# HAB_Schematic.net
KiCad netlist of a schematic drawn in Altium Designer
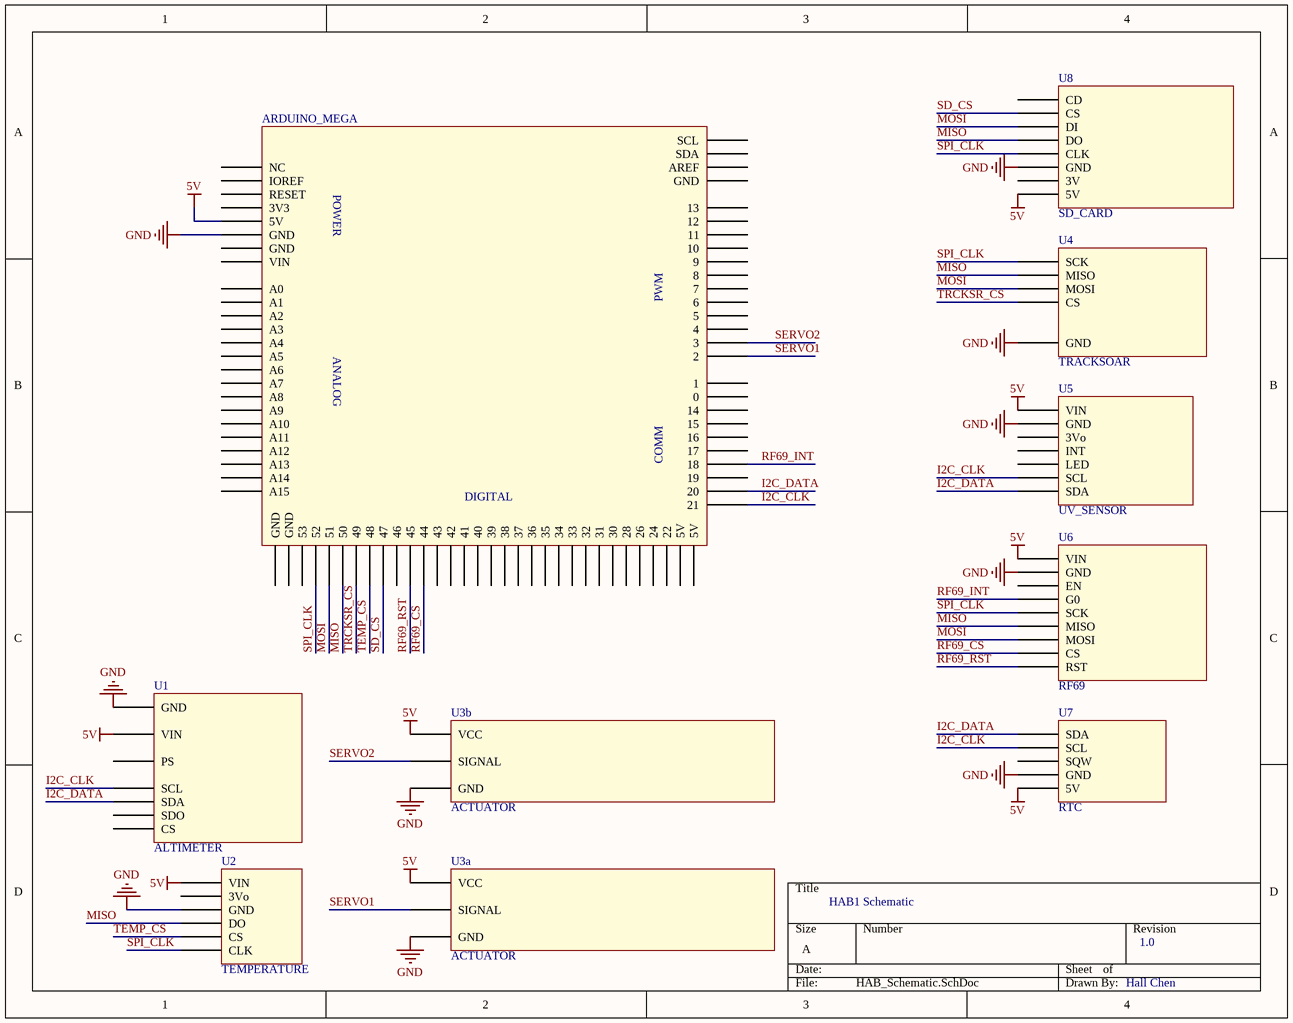
[diagram p0: HAB_Schematic.SchDoc]

(export (version "E")
  (design (tool "Eeschema 10.0.6"))
  (components
    (comp (ref "ARDUINO_MEGA")
      (value "ARDUINO_MEGA")
      (libsource (lib "HAB_Schematic_lib") (part "ARDUINO_MEGA"))
    )
    (comp (ref "U1") (value "ALTIMETER") (libsource (lib "HAB_Schematic_lib") (part "ALTIMETER")))
    (comp (ref "U2") (value "TEMPERATURE") (libsource (lib "HAB_Schematic_lib") (part "TEMPERATURE")))
    (comp (ref "U3a") (value "ACTUATOR") (libsource (lib "HAB_Schematic_lib") (part "ACTUATOR")))
    (comp (ref "U3b") (value "ACTUATOR") (libsource (lib "HAB_Schematic_lib") (part "ACTUATOR")))
    (comp (ref "U4") (value "TRACKSOAR") (libsource (lib "HAB_Schematic_lib") (part "TRACKSOAR")))
    (comp (ref "U5") (value "UV_SENSOR") (libsource (lib "HAB_Schematic_lib") (part "UV_SENSOR")))
    (comp (ref "U6") (value "RF69") (libsource (lib "HAB_Schematic_lib") (part "RF69")))
    (comp (ref "U7") (value "RTC") (libsource (lib "HAB_Schematic_lib") (part "RTC")))
    (comp (ref "U8") (value "SD_CARD") (libsource (lib "HAB_Schematic_lib") (part "SD_CARD")))
  )
  (nets
    (net (code "1") (name "/I2C_CLK") (class "Default")
      (node (ref "ARDUINO_MEGA") (pin "73") (pinfunction "21_73") (pintype "passive"))
      (node (ref "U1") (pin "4") (pinfunction "SCL_4") (pintype "passive"))
      (node (ref "U5") (pin "6") (pinfunction "SCL_6") (pintype "passive"))
      (node (ref "U7") (pin "2") (pinfunction "SCL_2") (pintype "passive"))
    )
    (net (code "2") (name "/I2C_DATA") (class "Default")
      (node (ref "ARDUINO_MEGA") (pin "72") (pinfunction "20_72") (pintype "passive"))
      (node (ref "U1") (pin "5") (pinfunction "SDA_5") (pintype "passive"))
      (node (ref "U5") (pin "7") (pinfunction "SDA_7") (pintype "passive"))
      (node (ref "U7") (pin "1") (pinfunction "SDA_1") (pintype "passive"))
    )
    (net (code "3") (name "/MISO") (class "Default")
      (node (ref "ARDUINO_MEGA") (pin "39") (pinfunction "50_39") (pintype "passive"))
      (node (ref "U2") (pin "4") (pinfunction "DO_4") (pintype "passive"))
      (node (ref "U4") (pin "1") (pinfunction "MISO_1") (pintype "passive"))
      (node (ref "U6") (pin "6") (pinfunction "MISO_6") (pintype "passive"))
      (node (ref "U8") (pin "4") (pinfunction "DO_4") (pintype "passive"))
    )
    (net (code "4") (name "/MOSI") (class "Default")
      (node (ref "ARDUINO_MEGA") (pin "40") (pinfunction "51_40") (pintype "passive"))
      (node (ref "U4") (pin "2") (pinfunction "MOSI_2") (pintype "passive"))
      (node (ref "U6") (pin "7") (pinfunction "MOSI_7") (pintype "passive"))
      (node (ref "U8") (pin "3") (pinfunction "DI_3") (pintype "passive"))
    )
    (net (code "5") (name "/RF69_CS") (class "Default")
      (node (ref "ARDUINO_MEGA") (pin "33") (pinfunction "44_33") (pintype "passive"))
      (node (ref "U6") (pin "8") (pinfunction "CS_8") (pintype "passive"))
    )
    (net (code "6") (name "/RF69_INT") (class "Default")
      (node (ref "ARDUINO_MEGA") (pin "70") (pinfunction "18_70") (pintype "passive"))
      (node (ref "U6") (pin "4") (pinfunction "G0_4") (pintype "passive"))
    )
    (net (code "7") (name "/RF69_RST") (class "Default")
      (node (ref "ARDUINO_MEGA") (pin "34") (pinfunction "45_34") (pintype "passive"))
      (node (ref "U6") (pin "9") (pinfunction "RST_9") (pintype "passive"))
    )
    (net (code "8") (name "/SD_CS") (class "Default")
      (node (ref "ARDUINO_MEGA") (pin "36") (pinfunction "47_36") (pintype "passive"))
      (node (ref "U8") (pin "2") (pinfunction "CS_2") (pintype "passive"))
    )
    (net (code "9") (name "/SERVO1") (class "Default")
      (node (ref "ARDUINO_MEGA") (pin "50") (pinfunction "2_50") (pintype "passive"))
      (node (ref "U3a") (pin "1") (pinfunction "SIGNAL_1") (pintype "passive"))
    )
    (net (code "10") (name "/SERVO2") (class "Default")
      (node (ref "ARDUINO_MEGA") (pin "51") (pinfunction "3_51") (pintype "passive"))
      (node (ref "U3b") (pin "1") (pinfunction "SIGNAL_1") (pintype "passive"))
    )
    (net (code "11") (name "/SPI_CLK") (class "Default")
      (node (ref "ARDUINO_MEGA") (pin "41") (pinfunction "52_41") (pintype "passive"))
      (node (ref "U2") (pin "6") (pinfunction "CLK_6") (pintype "passive"))
      (node (ref "U4") (pin "4") (pinfunction "SCK_4") (pintype "passive"))
      (node (ref "U6") (pin "5") (pinfunction "SCK_5") (pintype "passive"))
      (node (ref "U8") (pin "5") (pinfunction "CLK_5") (pintype "passive"))
    )
    (net (code "12") (name "/TEMP_CS") (class "Default")
      (node (ref "ARDUINO_MEGA") (pin "37") (pinfunction "48_37") (pintype "passive"))
      (node (ref "U2") (pin "5") (pinfunction "CS_5") (pintype "passive"))
    )
    (net (code "13") (name "/TRCKSR_CS") (class "Default")
      (node (ref "ARDUINO_MEGA") (pin "38") (pinfunction "49_38") (pintype "passive"))
      (node (ref "U4") (pin "3") (pinfunction "CS_3") (pintype "passive"))
    )
    (net (code "14") (name "5V") (class "Default")
      (node (ref "ARDUINO_MEGA") (pin "5") (pinfunction "5V_5") (pintype "passive"))
      (node (ref "U1") (pin "2") (pinfunction "VIN_2") (pintype "passive"))
      (node (ref "U2") (pin "1") (pinfunction "VIN_1") (pintype "passive"))
      (node (ref "U3a") (pin "0") (pinfunction "VCC_0") (pintype "passive"))
      (node (ref "U3b") (pin "0") (pinfunction "VCC_0") (pintype "passive"))
      (node (ref "U5") (pin "1") (pinfunction "VIN_1") (pintype "passive"))
      (node (ref "U6") (pin "1") (pinfunction "VIN_1") (pintype "passive"))
      (node (ref "U7") (pin "5") (pinfunction "5V_5") (pintype "passive"))
      (node (ref "U8") (pin "8") (pinfunction "5V_8") (pintype "passive"))
    )
    (net (code "15") (name "GND") (class "Default")
      (node (ref "ARDUINO_MEGA") (pin "6") (pinfunction "GND_6") (pintype "passive"))
      (node (ref "U1") (pin "1") (pinfunction "GND_1") (pintype "passive"))
      (node (ref "U2") (pin "3") (pinfunction "GND_3") (pintype "passive"))
      (node (ref "U3a") (pin "2") (pinfunction "GND_2") (pintype "passive"))
      (node (ref "U3b") (pin "2") (pinfunction "GND_2") (pintype "passive"))
      (node (ref "U4") (pin "5") (pinfunction "GND_5") (pintype "passive"))
      (node (ref "U5") (pin "2") (pinfunction "GND_2") (pintype "passive"))
      (node (ref "U6") (pin "2") (pinfunction "GND_2") (pintype "passive"))
      (node (ref "U7") (pin "4") (pinfunction "GND_4") (pintype "passive"))
      (node (ref "U8") (pin "6") (pinfunction "GND_6") (pintype "passive"))
    )
    (net (code "16") (name "unconnected-(ARDUINO_MEGA-0-Pad48)") (class "Default")
      (node (ref "ARDUINO_MEGA") (pin "48") (pinfunction "0_48") (pintype "passive"))
    )
    (net (code "17") (name "unconnected-(ARDUINO_MEGA-1-Pad49)") (class "Default")
      (node (ref "ARDUINO_MEGA") (pin "49") (pinfunction "1_49") (pintype "passive"))
    )
    (net (code "18") (name "unconnected-(ARDUINO_MEGA-3V3-Pad4)") (class "Default")
      (node (ref "ARDUINO_MEGA") (pin "4") (pinfunction "3V3_4") (pintype "passive"))
    )
    (net (code "19") (name "unconnected-(ARDUINO_MEGA-4-Pad52)") (class "Default")
      (node (ref "ARDUINO_MEGA") (pin "52") (pinfunction "4_52") (pintype "passive"))
    )
    (net (code "20") (name "unconnected-(ARDUINO_MEGA-5-Pad53)") (class "Default")
      (node (ref "ARDUINO_MEGA") (pin "53") (pinfunction "5_53") (pintype "passive"))
    )
    (net (code "21") (name "unconnected-(ARDUINO_MEGA-5V-Pad46)") (class "Default")
      (node (ref "ARDUINO_MEGA") (pin "46") (pinfunction "5V_46") (pintype "passive"))
    )
    (net (code "22") (name "unconnected-(ARDUINO_MEGA-5V-Pad47)") (class "Default")
      (node (ref "ARDUINO_MEGA") (pin "47") (pinfunction "5V_47") (pintype "passive"))
    )
    (net (code "23") (name "unconnected-(ARDUINO_MEGA-6-Pad54)") (class "Default")
      (node (ref "ARDUINO_MEGA") (pin "54") (pinfunction "6_54") (pintype "passive"))
    )
    (net (code "24") (name "unconnected-(ARDUINO_MEGA-7-Pad55)") (class "Default")
      (node (ref "ARDUINO_MEGA") (pin "55") (pinfunction "7_55") (pintype "passive"))
    )
    (net (code "25") (name "unconnected-(ARDUINO_MEGA-8-Pad56)") (class "Default")
      (node (ref "ARDUINO_MEGA") (pin "56") (pinfunction "8_56") (pintype "passive"))
    )
    (net (code "26") (name "unconnected-(ARDUINO_MEGA-9-Pad57)") (class "Default")
      (node (ref "ARDUINO_MEGA") (pin "57") (pinfunction "9_57") (pintype "passive"))
    )
    (net (code "27") (name "unconnected-(ARDUINO_MEGA-10-Pad58)") (class "Default")
      (node (ref "ARDUINO_MEGA") (pin "58") (pinfunction "10_58") (pintype "passive"))
    )
    (net (code "28") (name "unconnected-(ARDUINO_MEGA-11-Pad59)") (class "Default")
      (node (ref "ARDUINO_MEGA") (pin "59") (pinfunction "11_59") (pintype "passive"))
    )
    (net (code "29") (name "unconnected-(ARDUINO_MEGA-12-Pad60)") (class "Default")
      (node (ref "ARDUINO_MEGA") (pin "60") (pinfunction "12_60") (pintype "passive"))
    )
    (net (code "30") (name "unconnected-(ARDUINO_MEGA-13-Pad61)") (class "Default")
      (node (ref "ARDUINO_MEGA") (pin "61") (pinfunction "13_61") (pintype "passive"))
    )
    (net (code "31") (name "unconnected-(ARDUINO_MEGA-14-Pad66)") (class "Default")
      (node (ref "ARDUINO_MEGA") (pin "66") (pinfunction "14_66") (pintype "passive"))
    )
    (net (code "32") (name "unconnected-(ARDUINO_MEGA-15-Pad67)") (class "Default")
      (node (ref "ARDUINO_MEGA") (pin "67") (pinfunction "15_67") (pintype "passive"))
    )
    (net (code "33") (name "unconnected-(ARDUINO_MEGA-16-Pad68)") (class "Default")
      (node (ref "ARDUINO_MEGA") (pin "68") (pinfunction "16_68") (pintype "passive"))
    )
    (net (code "34") (name "unconnected-(ARDUINO_MEGA-17-Pad69)") (class "Default")
      (node (ref "ARDUINO_MEGA") (pin "69") (pinfunction "17_69") (pintype "passive"))
    )
    (net (code "35") (name "unconnected-(ARDUINO_MEGA-19-Pad71)") (class "Default")
      (node (ref "ARDUINO_MEGA") (pin "71") (pinfunction "19_71") (pintype "passive"))
    )
    (net (code "36") (name "unconnected-(ARDUINO_MEGA-22-Pad45)") (class "Default")
      (node (ref "ARDUINO_MEGA") (pin "45") (pinfunction "22_45") (pintype "passive"))
    )
    (net (code "37") (name "unconnected-(ARDUINO_MEGA-24-Pad44)") (class "Default")
      (node (ref "ARDUINO_MEGA") (pin "44") (pinfunction "24_44") (pintype "passive"))
    )
    (net (code "38") (name "unconnected-(ARDUINO_MEGA-26-Pad43)") (class "Default")
      (node (ref "ARDUINO_MEGA") (pin "43") (pinfunction "26_43") (pintype "passive"))
    )
    (net (code "39") (name "unconnected-(ARDUINO_MEGA-28-Pad42)") (class "Default")
      (node (ref "ARDUINO_MEGA") (pin "42") (pinfunction "28_42") (pintype "passive"))
    )
    (net (code "40") (name "unconnected-(ARDUINO_MEGA-30-Pad19)") (class "Default")
      (node (ref "ARDUINO_MEGA") (pin "19") (pinfunction "30_19") (pintype "passive"))
    )
    (net (code "41") (name "unconnected-(ARDUINO_MEGA-31-Pad20)") (class "Default")
      (node (ref "ARDUINO_MEGA") (pin "20") (pinfunction "31_20") (pintype "passive"))
    )
    (net (code "42") (name "unconnected-(ARDUINO_MEGA-32-Pad21)") (class "Default")
      (node (ref "ARDUINO_MEGA") (pin "21") (pinfunction "32_21") (pintype "passive"))
    )
    (net (code "43") (name "unconnected-(ARDUINO_MEGA-33-Pad22)") (class "Default")
      (node (ref "ARDUINO_MEGA") (pin "22") (pinfunction "33_22") (pintype "passive"))
    )
    (net (code "44") (name "unconnected-(ARDUINO_MEGA-34-Pad23)") (class "Default")
      (node (ref "ARDUINO_MEGA") (pin "23") (pinfunction "34_23") (pintype "passive"))
    )
    (net (code "45") (name "unconnected-(ARDUINO_MEGA-35-Pad24)") (class "Default")
      (node (ref "ARDUINO_MEGA") (pin "24") (pinfunction "35_24") (pintype "passive"))
    )
    (net (code "46") (name "unconnected-(ARDUINO_MEGA-36-Pad25)") (class "Default")
      (node (ref "ARDUINO_MEGA") (pin "25") (pinfunction "36_25") (pintype "passive"))
    )
    (net (code "47") (name "unconnected-(ARDUINO_MEGA-37-Pad26)") (class "Default")
      (node (ref "ARDUINO_MEGA") (pin "26") (pinfunction "37_26") (pintype "passive"))
    )
    (net (code "48") (name "unconnected-(ARDUINO_MEGA-38-Pad27)") (class "Default")
      (node (ref "ARDUINO_MEGA") (pin "27") (pinfunction "38_27") (pintype "passive"))
    )
    (net (code "49") (name "unconnected-(ARDUINO_MEGA-39-Pad28)") (class "Default")
      (node (ref "ARDUINO_MEGA") (pin "28") (pinfunction "39_28") (pintype "passive"))
    )
    (net (code "50") (name "unconnected-(ARDUINO_MEGA-40-Pad29)") (class "Default")
      (node (ref "ARDUINO_MEGA") (pin "29") (pinfunction "40_29") (pintype "passive"))
    )
    (net (code "51") (name "unconnected-(ARDUINO_MEGA-41-Pad30)") (class "Default")
      (node (ref "ARDUINO_MEGA") (pin "30") (pinfunction "41_30") (pintype "passive"))
    )
    (net (code "52") (name "unconnected-(ARDUINO_MEGA-42-Pad31)") (class "Default")
      (node (ref "ARDUINO_MEGA") (pin "31") (pinfunction "42_31") (pintype "passive"))
    )
    (net (code "53") (name "unconnected-(ARDUINO_MEGA-43-Pad32)") (class "Default")
      (node (ref "ARDUINO_MEGA") (pin "32") (pinfunction "43_32") (pintype "passive"))
    )
    (net (code "54") (name "unconnected-(ARDUINO_MEGA-46-Pad35)") (class "Default")
      (node (ref "ARDUINO_MEGA") (pin "35") (pinfunction "46_35") (pintype "passive"))
    )
    (net (code "55") (name "unconnected-(ARDUINO_MEGA-53-Pad18)") (class "Default")
      (node (ref "ARDUINO_MEGA") (pin "18") (pinfunction "53_18") (pintype "passive"))
    )
    (net (code "56") (name "unconnected-(ARDUINO_MEGA-A0-Pad9)") (class "Default")
      (node (ref "ARDUINO_MEGA") (pin "9") (pinfunction "A0_9") (pintype "passive"))
    )
    (net (code "57") (name "unconnected-(ARDUINO_MEGA-A1-Pad10)") (class "Default")
      (node (ref "ARDUINO_MEGA") (pin "10") (pinfunction "A1_10") (pintype "passive"))
    )
    (net (code "58") (name "unconnected-(ARDUINO_MEGA-A2-Pad2)") (class "Default")
      (node (ref "ARDUINO_MEGA") (pin "2") (pinfunction "A2_2") (pintype "passive"))
    )
    (net (code "59") (name "unconnected-(ARDUINO_MEGA-A3-Pad3)") (class "Default")
      (node (ref "ARDUINO_MEGA") (pin "3") (pinfunction "A3_3") (pintype "passive"))
    )
    (net (code "60") (name "unconnected-(ARDUINO_MEGA-A4-Pad4)") (class "Default")
      (node (ref "ARDUINO_MEGA") (pin "4") (pinfunction "A4_4") (pintype "passive"))
    )
    (net (code "61") (name "unconnected-(ARDUINO_MEGA-A5-Pad5)") (class "Default")
      (node (ref "ARDUINO_MEGA") (pin "5") (pinfunction "A5_5") (pintype "passive"))
    )
    (net (code "62") (name "unconnected-(ARDUINO_MEGA-A6-Pad6)") (class "Default")
      (node (ref "ARDUINO_MEGA") (pin "6") (pinfunction "A6_6") (pintype "passive"))
    )
    (net (code "63") (name "unconnected-(ARDUINO_MEGA-A7-Pad7)") (class "Default")
      (node (ref "ARDUINO_MEGA") (pin "7") (pinfunction "A7_7") (pintype "passive"))
    )
    (net (code "64") (name "unconnected-(ARDUINO_MEGA-A8-Pad8)") (class "Default")
      (node (ref "ARDUINO_MEGA") (pin "8") (pinfunction "A8_8") (pintype "passive"))
    )
    (net (code "65") (name "unconnected-(ARDUINO_MEGA-A9-Pad9)") (class "Default")
      (node (ref "ARDUINO_MEGA") (pin "9") (pinfunction "A9_9") (pintype "passive"))
    )
    (net (code "66") (name "unconnected-(ARDUINO_MEGA-A10-Pad10)") (class "Default")
      (node (ref "ARDUINO_MEGA") (pin "10") (pinfunction "A10_10") (pintype "passive"))
    )
    (net (code "67") (name "unconnected-(ARDUINO_MEGA-A11-Pad11)") (class "Default")
      (node (ref "ARDUINO_MEGA") (pin "11") (pinfunction "A11_11") (pintype "passive"))
    )
    (net (code "68") (name "unconnected-(ARDUINO_MEGA-A12-Pad12)") (class "Default")
      (node (ref "ARDUINO_MEGA") (pin "12") (pinfunction "A12_12") (pintype "passive"))
    )
    (net (code "69") (name "unconnected-(ARDUINO_MEGA-A13-Pad13)") (class "Default")
      (node (ref "ARDUINO_MEGA") (pin "13") (pinfunction "A13_13") (pintype "passive"))
    )
    (net (code "70") (name "unconnected-(ARDUINO_MEGA-A14-Pad14)") (class "Default")
      (node (ref "ARDUINO_MEGA") (pin "14") (pinfunction "A14_14") (pintype "passive"))
    )
    (net (code "71") (name "unconnected-(ARDUINO_MEGA-A15-Pad15)") (class "Default")
      (node (ref "ARDUINO_MEGA") (pin "15") (pinfunction "A15_15") (pintype "passive"))
    )
    (net (code "72") (name "unconnected-(ARDUINO_MEGA-AREF-Pad63)") (class "Default")
      (node (ref "ARDUINO_MEGA") (pin "63") (pinfunction "AREF_63") (pintype "passive"))
    )
    (net (code "73") (name "unconnected-(ARDUINO_MEGA-GND-Pad7)") (class "Default")
      (node (ref "ARDUINO_MEGA") (pin "7") (pinfunction "GND_7") (pintype "passive"))
    )
    (net (code "74") (name "unconnected-(ARDUINO_MEGA-GND-Pad16)") (class "Default")
      (node (ref "ARDUINO_MEGA") (pin "16") (pinfunction "GND_16") (pintype "passive"))
    )
    (net (code "75") (name "unconnected-(ARDUINO_MEGA-GND-Pad17)") (class "Default")
      (node (ref "ARDUINO_MEGA") (pin "17") (pinfunction "GND_17") (pintype "passive"))
    )
    (net (code "76") (name "unconnected-(ARDUINO_MEGA-GND-Pad62)") (class "Default")
      (node (ref "ARDUINO_MEGA") (pin "62") (pinfunction "GND_62") (pintype "passive"))
    )
    (net (code "77") (name "unconnected-(ARDUINO_MEGA-IOREF-Pad2)") (class "Default")
      (node (ref "ARDUINO_MEGA") (pin "2") (pinfunction "IOREF_2") (pintype "passive"))
    )
    (net (code "78") (name "unconnected-(ARDUINO_MEGA-NC-Pad1)") (class "Default")
      (node (ref "ARDUINO_MEGA") (pin "1") (pinfunction "NC_1") (pintype "passive"))
    )
    (net (code "79") (name "unconnected-(ARDUINO_MEGA-RESET-Pad3)") (class "Default")
      (node (ref "ARDUINO_MEGA") (pin "3") (pinfunction "RESET_3") (pintype "passive"))
    )
    (net (code "80") (name "unconnected-(ARDUINO_MEGA-SCL-Pad65)") (class "Default")
      (node (ref "ARDUINO_MEGA") (pin "65") (pinfunction "SCL_65") (pintype "passive"))
    )
    (net (code "81") (name "unconnected-(ARDUINO_MEGA-SDA-Pad64)") (class "Default")
      (node (ref "ARDUINO_MEGA") (pin "64") (pinfunction "SDA_64") (pintype "passive"))
    )
    (net (code "82") (name "unconnected-(ARDUINO_MEGA-VIN-Pad8)") (class "Default")
      (node (ref "ARDUINO_MEGA") (pin "8") (pinfunction "VIN_8") (pintype "passive"))
    )
    (net (code "83") (name "unconnected-(U1-CS-Pad7)") (class "Default")
      (node (ref "U1") (pin "7") (pinfunction "CS_7") (pintype "passive"))
    )
    (net (code "84") (name "unconnected-(U1-PS-Pad3)") (class "Default")
      (node (ref "U1") (pin "3") (pinfunction "PS_3") (pintype "passive"))
    )
    (net (code "85") (name "unconnected-(U1-SDO-Pad6)") (class "Default")
      (node (ref "U1") (pin "6") (pinfunction "SDO_6") (pintype "passive"))
    )
    (net (code "86") (name "unconnected-(U2-3Vo-Pad2)") (class "Default")
      (node (ref "U2") (pin "2") (pinfunction "3Vo_2") (pintype "passive"))
    )
    (net (code "87") (name "unconnected-(U5-3Vo-Pad3)") (class "Default")
      (node (ref "U5") (pin "3") (pinfunction "3Vo_3") (pintype "passive"))
    )
    (net (code "88") (name "unconnected-(U5-INT-Pad4)") (class "Default")
      (node (ref "U5") (pin "4") (pinfunction "INT_4") (pintype "passive"))
    )
    (net (code "89") (name "unconnected-(U5-LED-Pad5)") (class "Default")
      (node (ref "U5") (pin "5") (pinfunction "LED_5") (pintype "passive"))
    )
    (net (code "90") (name "unconnected-(U6-EN-Pad3)") (class "Default")
      (node (ref "U6") (pin "3") (pinfunction "EN_3") (pintype "passive"))
    )
    (net (code "91") (name "unconnected-(U7-SQW-Pad3)") (class "Default")
      (node (ref "U7") (pin "3") (pinfunction "SQW_3") (pintype "passive"))
    )
    (net (code "92") (name "unconnected-(U8-3V-Pad7)") (class "Default")
      (node (ref "U8") (pin "7") (pinfunction "3V_7") (pintype "passive"))
    )
    (net (code "93") (name "unconnected-(U8-CD-Pad1)") (class "Default")
      (node (ref "U8") (pin "1") (pinfunction "CD_1") (pintype "passive"))
    )
  )
)
